# PhotonOnAStick.net
KiCad netlist of a schematic drawn in EAGLE
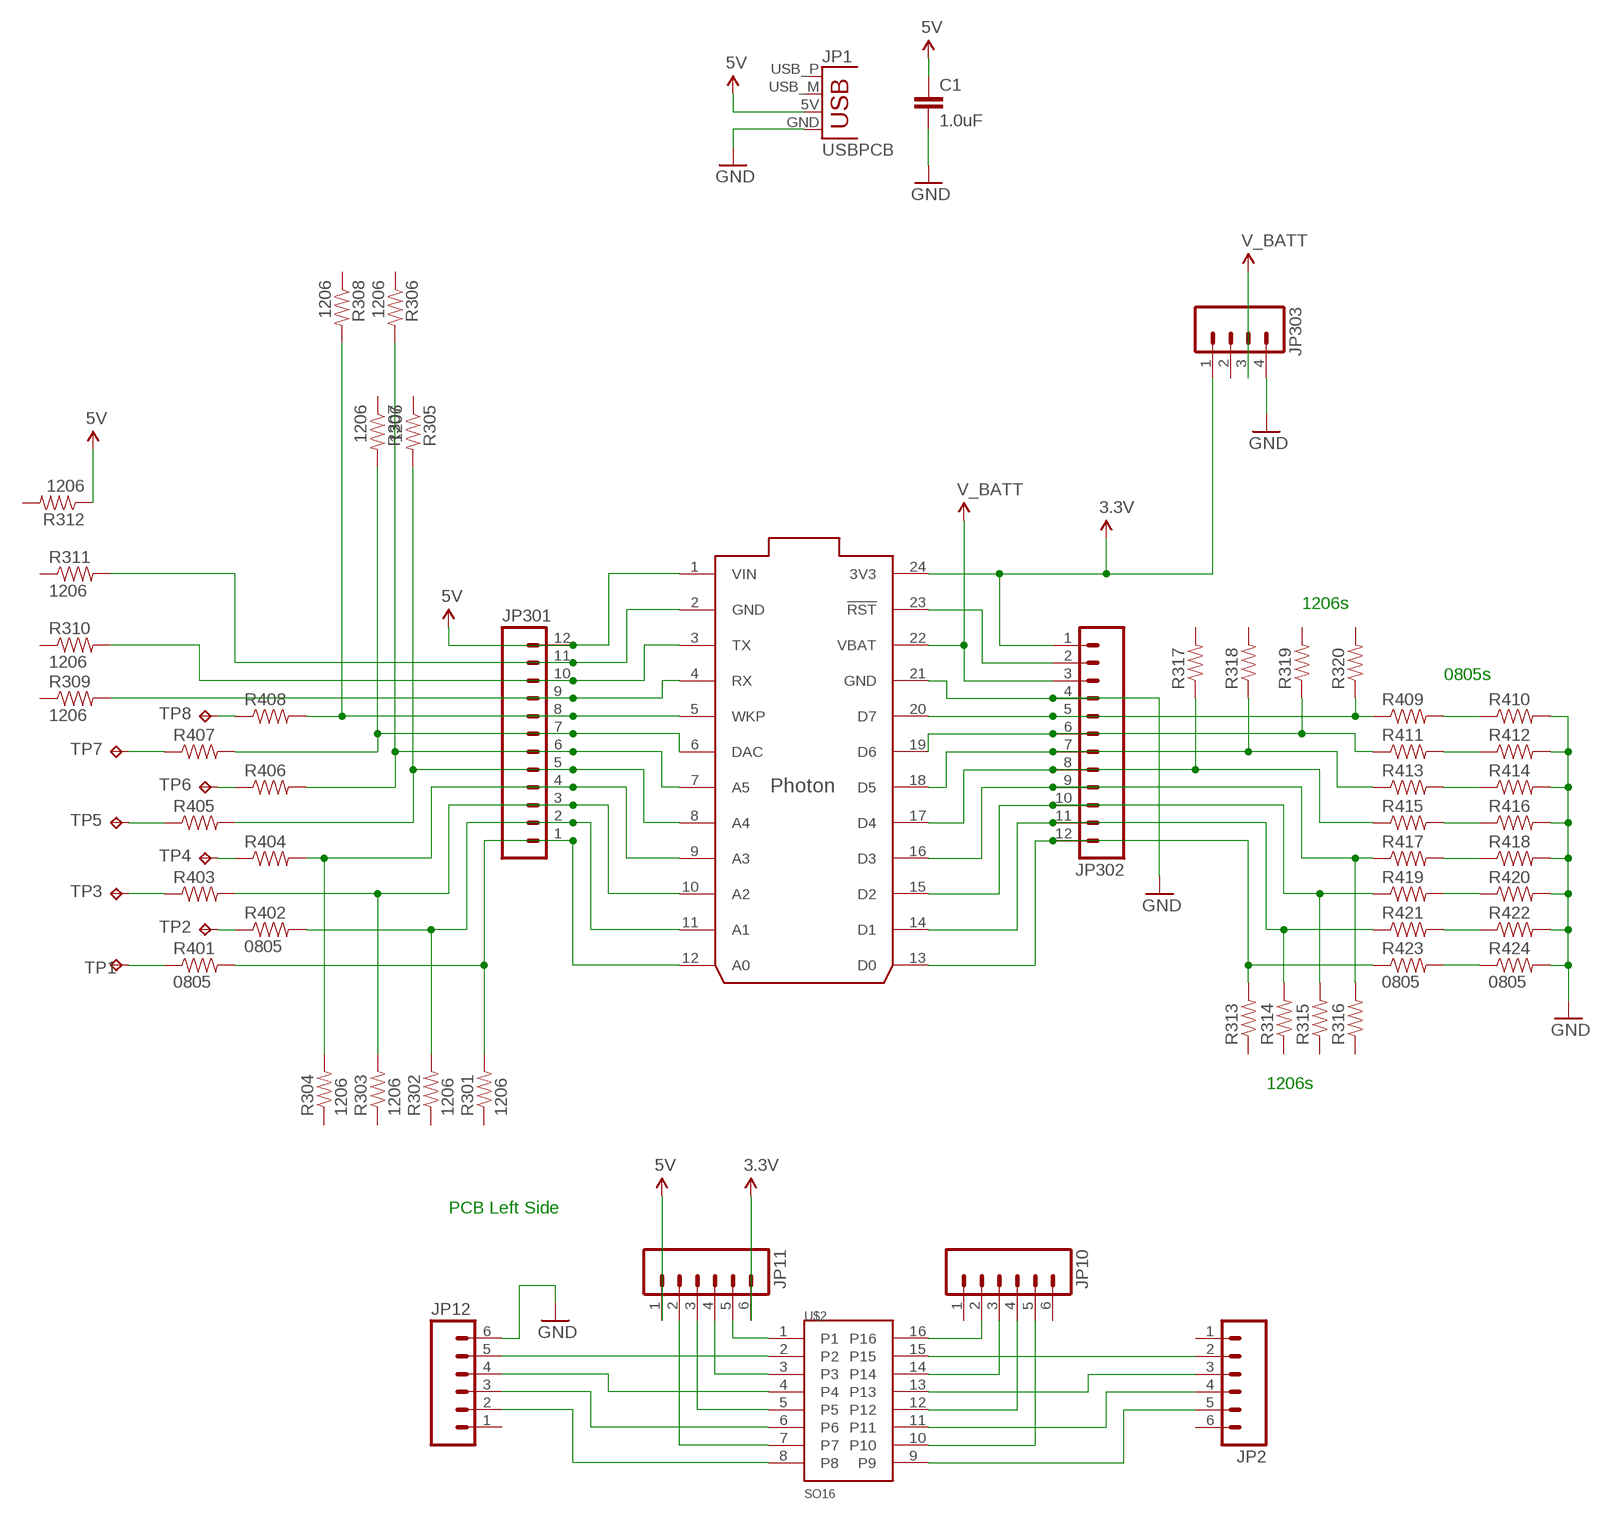
[diagram p0: schematic, sheet 1, part 1 of 2]
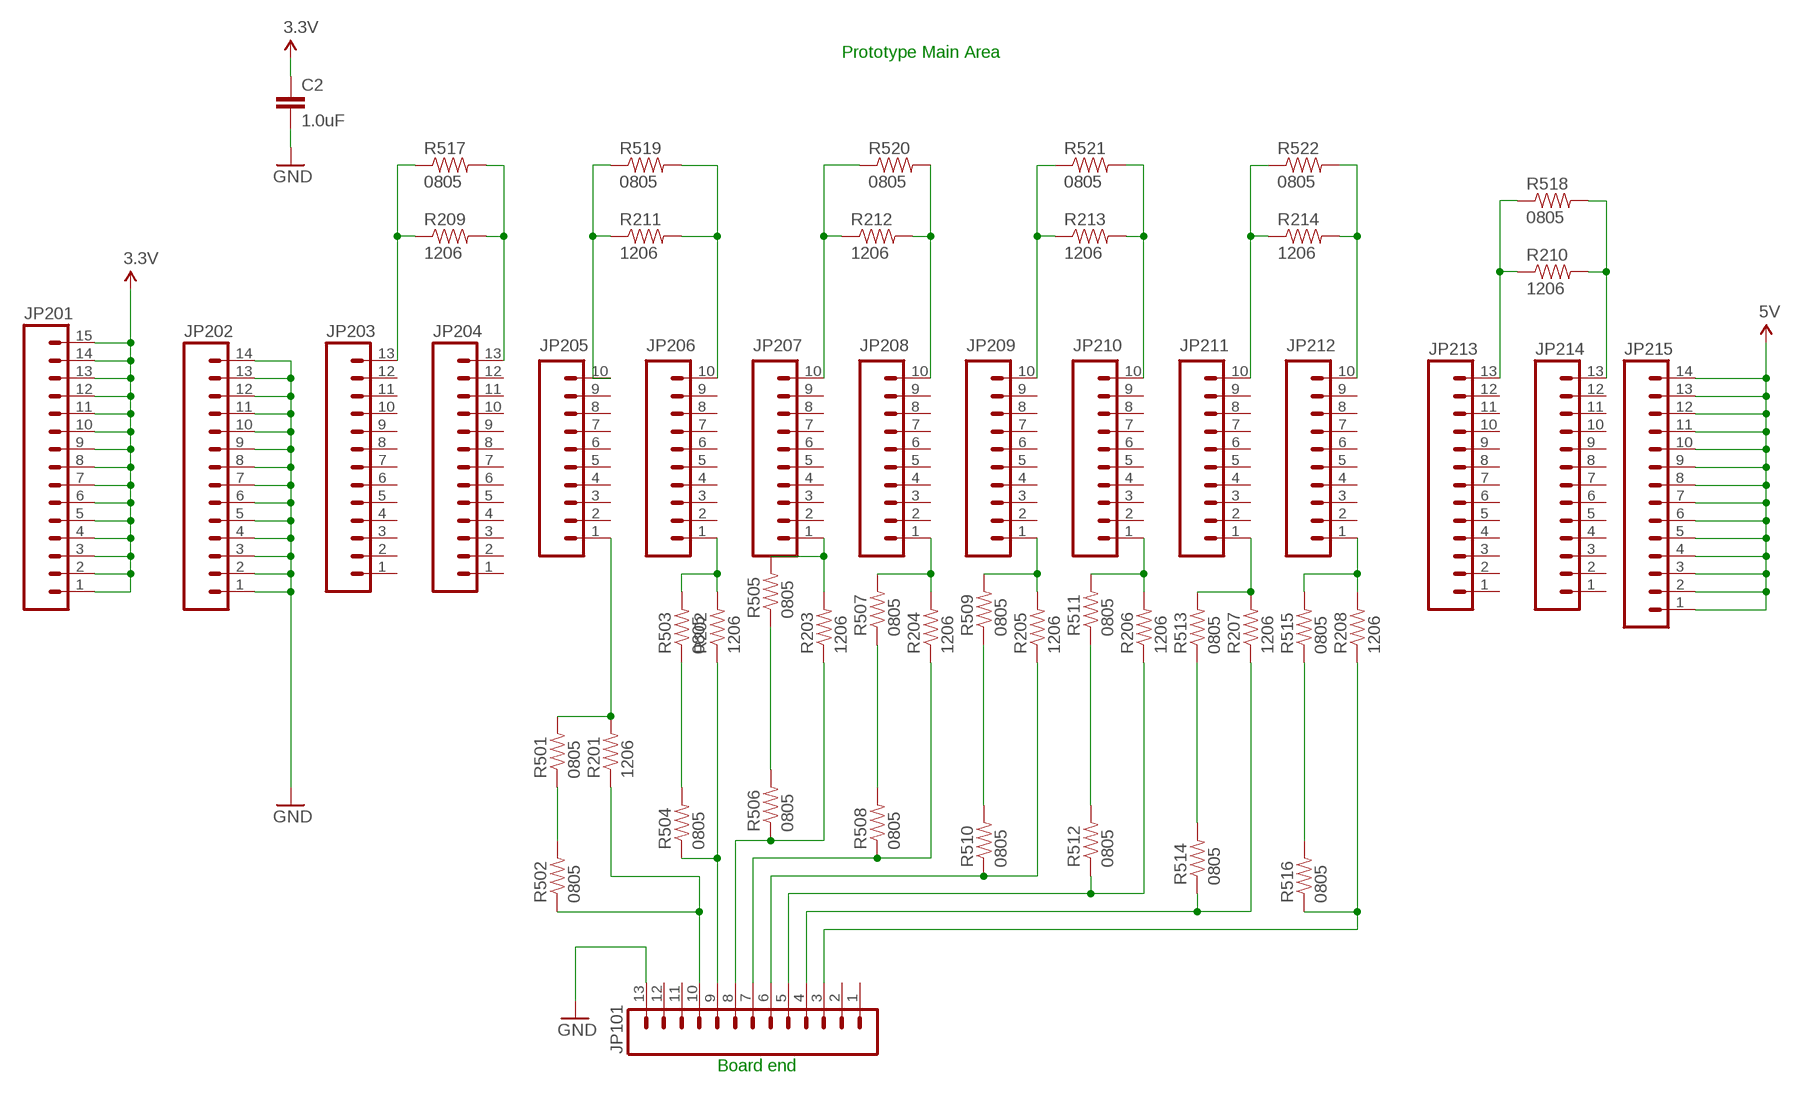
[diagram p1: schematic, sheet 1, part 2 of 2]

(export (version "E")
  (design (tool "Eeschema 10.0.6"))
  (components
    (comp (ref "C1")
      (value "1.0uF")
      (footprint "eagle-import:0805-CAP")
      (libsource (lib "eagle-import") (part "1.0UF-25V-+80/-20(0805){dblquote}"))
    )
    (comp (ref "C2")
      (value "1.0uF")
      (footprint "eagle-import:0805-CAP")
      (libsource (lib "eagle-import") (part "1.0UF-25V-+80/-20(0805){dblquote}"))
    )
    (comp (ref "JP1")
      (value "USBPCB")
      (footprint "eagle-import:USB-A-PCB")
      (libsource (lib "eagle-import") (part "USBPCB"))
    )
    (comp (ref "JP2")
      (value "M06SILK_FEMALE_PTH")
      (footprint "eagle-import:1X06")
      (libsource (lib "eagle-import") (part "M06SILK_FEMALE_PTH"))
    )
    (comp (ref "JP10")
      (value "M06SILK_FEMALE_PTH")
      (footprint "eagle-import:1X06")
      (libsource (lib "eagle-import") (part "M06SILK_FEMALE_PTH"))
    )
    (comp (ref "JP11")
      (value "M06SILK_FEMALE_PTH")
      (footprint "eagle-import:1X06")
      (libsource (lib "eagle-import") (part "M06SILK_FEMALE_PTH"))
    )
    (comp (ref "JP12")
      (value "M06SILK_FEMALE_PTH")
      (footprint "eagle-import:1X06")
      (libsource (lib "eagle-import") (part "M06SILK_FEMALE_PTH"))
    )
    (comp (ref "JP101")
      (value "M13")
      (footprint "eagle-import:1X13")
      (libsource (lib "eagle-import") (part "M13"))
    )
    (comp (ref "JP201")
      (value "M15")
      (footprint "eagle-import:1X15")
      (libsource (lib "eagle-import") (part "M15"))
    )
    (comp (ref "JP202")
      (value "M14")
      (footprint "eagle-import:1X14")
      (libsource (lib "eagle-import") (part "M14"))
    )
    (comp (ref "JP203")
      (value "M13")
      (footprint "eagle-import:1X13")
      (libsource (lib "eagle-import") (part "M13"))
    )
    (comp (ref "JP204")
      (value "M13")
      (footprint "eagle-import:1X13")
      (libsource (lib "eagle-import") (part "M13"))
    )
    (comp (ref "JP205")
      (value "M10SILK_FEMALE_PTH")
      (footprint "eagle-import:1X10")
      (libsource (lib "eagle-import") (part "M10SILK_FEMALE_PTH"))
    )
    (comp (ref "JP206")
      (value "M10SILK_FEMALE_PTH")
      (footprint "eagle-import:1X10")
      (libsource (lib "eagle-import") (part "M10SILK_FEMALE_PTH"))
    )
    (comp (ref "JP207")
      (value "M10SILK_FEMALE_PTH")
      (footprint "eagle-import:1X10")
      (libsource (lib "eagle-import") (part "M10SILK_FEMALE_PTH"))
    )
    (comp (ref "JP208")
      (value "M10SILK_FEMALE_PTH")
      (footprint "eagle-import:1X10")
      (libsource (lib "eagle-import") (part "M10SILK_FEMALE_PTH"))
    )
    (comp (ref "JP209")
      (value "M10SILK_FEMALE_PTH")
      (footprint "eagle-import:1X10")
      (libsource (lib "eagle-import") (part "M10SILK_FEMALE_PTH"))
    )
    (comp (ref "JP210")
      (value "M10SILK_FEMALE_PTH")
      (footprint "eagle-import:1X10")
      (libsource (lib "eagle-import") (part "M10SILK_FEMALE_PTH"))
    )
    (comp (ref "JP211")
      (value "M10SILK_FEMALE_PTH")
      (footprint "eagle-import:1X10")
      (libsource (lib "eagle-import") (part "M10SILK_FEMALE_PTH"))
    )
    (comp (ref "JP212")
      (value "M10SILK_FEMALE_PTH")
      (footprint "eagle-import:1X10")
      (libsource (lib "eagle-import") (part "M10SILK_FEMALE_PTH"))
    )
    (comp (ref "JP213")
      (value "M13")
      (footprint "eagle-import:1X13")
      (libsource (lib "eagle-import") (part "M13"))
    )
    (comp (ref "JP214")
      (value "M13")
      (footprint "eagle-import:1X13")
      (libsource (lib "eagle-import") (part "M13"))
    )
    (comp (ref "JP215")
      (value "M14")
      (footprint "eagle-import:1X14")
      (libsource (lib "eagle-import") (part "M14"))
    )
    (comp (ref "JP301")
      (value "M12PTH")
      (footprint "eagle-import:1X12")
      (libsource (lib "eagle-import") (part "M12PTH"))
    )
    (comp (ref "JP302")
      (value "M12PTH")
      (footprint "eagle-import:1X12")
      (libsource (lib "eagle-import") (part "M12PTH"))
    )
    (comp (ref "JP303")
      (value "M04PTH")
      (footprint "eagle-import:1X04")
      (libsource (lib "eagle-import") (part "M04PTH"))
    )
    (comp (ref "R201")
      (value "1206")
      (footprint "eagle-import:1206")
      (libsource (lib "eagle-import") (part "RESISTOR1206"))
    )
    (comp (ref "R202")
      (value "1206")
      (footprint "eagle-import:1206")
      (libsource (lib "eagle-import") (part "RESISTOR1206"))
    )
    (comp (ref "R203")
      (value "1206")
      (footprint "eagle-import:1206")
      (libsource (lib "eagle-import") (part "RESISTOR1206"))
    )
    (comp (ref "R204")
      (value "1206")
      (footprint "eagle-import:1206")
      (libsource (lib "eagle-import") (part "RESISTOR1206"))
    )
    (comp (ref "R205")
      (value "1206")
      (footprint "eagle-import:1206")
      (libsource (lib "eagle-import") (part "RESISTOR1206"))
    )
    (comp (ref "R206")
      (value "1206")
      (footprint "eagle-import:1206")
      (libsource (lib "eagle-import") (part "RESISTOR1206"))
    )
    (comp (ref "R207")
      (value "1206")
      (footprint "eagle-import:1206")
      (libsource (lib "eagle-import") (part "RESISTOR1206"))
    )
    (comp (ref "R208")
      (value "1206")
      (footprint "eagle-import:1206")
      (libsource (lib "eagle-import") (part "RESISTOR1206"))
    )
    (comp (ref "R209")
      (value "1206")
      (footprint "eagle-import:1206")
      (libsource (lib "eagle-import") (part "RESISTOR1206"))
    )
    (comp (ref "R210")
      (value "1206")
      (footprint "eagle-import:1206")
      (libsource (lib "eagle-import") (part "RESISTOR1206"))
    )
    (comp (ref "R211")
      (value "1206")
      (footprint "eagle-import:1206")
      (libsource (lib "eagle-import") (part "RESISTOR1206"))
    )
    (comp (ref "R212")
      (value "1206")
      (footprint "eagle-import:1206")
      (libsource (lib "eagle-import") (part "RESISTOR1206"))
    )
    (comp (ref "R213")
      (value "1206")
      (footprint "eagle-import:1206")
      (libsource (lib "eagle-import") (part "RESISTOR1206"))
    )
    (comp (ref "R214")
      (value "1206")
      (footprint "eagle-import:1206")
      (libsource (lib "eagle-import") (part "RESISTOR1206"))
    )
    (comp (ref "R301")
      (value "1206")
      (footprint "eagle-import:1206")
      (libsource (lib "eagle-import") (part "RESISTOR1206"))
    )
    (comp (ref "R302")
      (value "1206")
      (footprint "eagle-import:1206")
      (libsource (lib "eagle-import") (part "RESISTOR1206"))
    )
    (comp (ref "R303")
      (value "1206")
      (footprint "eagle-import:1206")
      (libsource (lib "eagle-import") (part "RESISTOR1206"))
    )
    (comp (ref "R304")
      (value "1206")
      (footprint "eagle-import:1206")
      (libsource (lib "eagle-import") (part "RESISTOR1206"))
    )
    (comp (ref "R305")
      (value "1206")
      (footprint "eagle-import:1206")
      (libsource (lib "eagle-import") (part "RESISTOR1206"))
    )
    (comp (ref "R306")
      (value "1206")
      (footprint "eagle-import:1206")
      (libsource (lib "eagle-import") (part "RESISTOR1206"))
    )
    (comp (ref "R307")
      (value "1206")
      (footprint "eagle-import:1206")
      (libsource (lib "eagle-import") (part "RESISTOR1206"))
    )
    (comp (ref "R308")
      (value "1206")
      (footprint "eagle-import:1206")
      (libsource (lib "eagle-import") (part "RESISTOR1206"))
    )
    (comp (ref "R309")
      (value "1206")
      (footprint "eagle-import:1206")
      (libsource (lib "eagle-import") (part "RESISTOR1206"))
    )
    (comp (ref "R310")
      (value "1206")
      (footprint "eagle-import:1206")
      (libsource (lib "eagle-import") (part "RESISTOR1206"))
    )
    (comp (ref "R311")
      (value "1206")
      (footprint "eagle-import:1206")
      (libsource (lib "eagle-import") (part "RESISTOR1206"))
    )
    (comp (ref "R312")
      (value "1206")
      (footprint "eagle-import:1206")
      (libsource (lib "eagle-import") (part "RESISTOR1206"))
    )
    (comp (ref "R313")
      (value "1206")
      (footprint "eagle-import:1206")
      (libsource (lib "eagle-import") (part "RESISTOR1206"))
    )
    (comp (ref "R314")
      (value "1206")
      (footprint "eagle-import:1206")
      (libsource (lib "eagle-import") (part "RESISTOR1206"))
    )
    (comp (ref "R315")
      (value "1206")
      (footprint "eagle-import:1206")
      (libsource (lib "eagle-import") (part "RESISTOR1206"))
    )
    (comp (ref "R316")
      (value "1206")
      (footprint "eagle-import:1206")
      (libsource (lib "eagle-import") (part "RESISTOR1206"))
    )
    (comp (ref "R317")
      (value "1206")
      (footprint "eagle-import:1206")
      (libsource (lib "eagle-import") (part "RESISTOR1206"))
    )
    (comp (ref "R318")
      (value "1206")
      (footprint "eagle-import:1206")
      (libsource (lib "eagle-import") (part "RESISTOR1206"))
    )
    (comp (ref "R319")
      (value "1206")
      (footprint "eagle-import:1206")
      (libsource (lib "eagle-import") (part "RESISTOR1206"))
    )
    (comp (ref "R320")
      (value "1206")
      (footprint "eagle-import:1206")
      (libsource (lib "eagle-import") (part "RESISTOR1206"))
    )
    (comp (ref "R401")
      (value "0805")
      (footprint "eagle-import:0805")
      (libsource (lib "eagle-import") (part "RESISTOR0805-RES"))
    )
    (comp (ref "R402")
      (value "0805")
      (footprint "eagle-import:0805")
      (libsource (lib "eagle-import") (part "RESISTOR0805-RES"))
    )
    (comp (ref "R403")
      (value "0805")
      (footprint "eagle-import:0805")
      (libsource (lib "eagle-import") (part "RESISTOR0805-RES"))
    )
    (comp (ref "R404")
      (value "0805")
      (footprint "eagle-import:0805")
      (libsource (lib "eagle-import") (part "RESISTOR0805-RES"))
    )
    (comp (ref "R405")
      (value "0805")
      (footprint "eagle-import:0805")
      (libsource (lib "eagle-import") (part "RESISTOR0805-RES"))
    )
    (comp (ref "R406")
      (value "0805")
      (footprint "eagle-import:0805")
      (libsource (lib "eagle-import") (part "RESISTOR0805-RES"))
    )
    (comp (ref "R407")
      (value "0805")
      (footprint "eagle-import:0805")
      (libsource (lib "eagle-import") (part "RESISTOR0805-RES"))
    )
    (comp (ref "R408")
      (value "0805")
      (footprint "eagle-import:0805")
      (libsource (lib "eagle-import") (part "RESISTOR0805-RES"))
    )
    (comp (ref "R409")
      (value "0805")
      (footprint "eagle-import:0805")
      (libsource (lib "eagle-import") (part "RESISTOR0805-RES"))
    )
    (comp (ref "R410")
      (value "0805")
      (footprint "eagle-import:0805")
      (libsource (lib "eagle-import") (part "RESISTOR0805-RES"))
    )
    (comp (ref "R411")
      (value "0805")
      (footprint "eagle-import:0805")
      (libsource (lib "eagle-import") (part "RESISTOR0805-RES"))
    )
    (comp (ref "R412")
      (value "0805")
      (footprint "eagle-import:0805")
      (libsource (lib "eagle-import") (part "RESISTOR0805-RES"))
    )
    (comp (ref "R413")
      (value "0805")
      (footprint "eagle-import:0805")
      (libsource (lib "eagle-import") (part "RESISTOR0805-RES"))
    )
    (comp (ref "R414")
      (value "0805")
      (footprint "eagle-import:0805")
      (libsource (lib "eagle-import") (part "RESISTOR0805-RES"))
    )
    (comp (ref "R415")
      (value "0805")
      (footprint "eagle-import:0805")
      (libsource (lib "eagle-import") (part "RESISTOR0805-RES"))
    )
    (comp (ref "R416")
      (value "0805")
      (footprint "eagle-import:0805")
      (libsource (lib "eagle-import") (part "RESISTOR0805-RES"))
    )
    (comp (ref "R417")
      (value "0805")
      (footprint "eagle-import:0805")
      (libsource (lib "eagle-import") (part "RESISTOR0805-RES"))
    )
    (comp (ref "R418")
      (value "0805")
      (footprint "eagle-import:0805")
      (libsource (lib "eagle-import") (part "RESISTOR0805-RES"))
    )
    (comp (ref "R419")
      (value "0805")
      (footprint "eagle-import:0805")
      (libsource (lib "eagle-import") (part "RESISTOR0805-RES"))
    )
    (comp (ref "R420")
      (value "0805")
      (footprint "eagle-import:0805")
      (libsource (lib "eagle-import") (part "RESISTOR0805-RES"))
    )
    (comp (ref "R421")
      (value "0805")
      (footprint "eagle-import:0805")
      (libsource (lib "eagle-import") (part "RESISTOR0805-RES"))
    )
    (comp (ref "R422")
      (value "0805")
      (footprint "eagle-import:0805")
      (libsource (lib "eagle-import") (part "RESISTOR0805-RES"))
    )
    (comp (ref "R423")
      (value "0805")
      (footprint "eagle-import:0805")
      (libsource (lib "eagle-import") (part "RESISTOR0805-RES"))
    )
    (comp (ref "R424")
      (value "0805")
      (footprint "eagle-import:0805")
      (libsource (lib "eagle-import") (part "RESISTOR0805-RES"))
    )
    (comp (ref "R501")
      (value "0805")
      (footprint "eagle-import:0805")
      (libsource (lib "eagle-import") (part "RESISTOR0805-RES"))
    )
    (comp (ref "R502")
      (value "0805")
      (footprint "eagle-import:0805")
      (libsource (lib "eagle-import") (part "RESISTOR0805-RES"))
    )
    (comp (ref "R503")
      (value "0805")
      (footprint "eagle-import:0805")
      (libsource (lib "eagle-import") (part "RESISTOR0805-RES"))
    )
    (comp (ref "R504")
      (value "0805")
      (footprint "eagle-import:0805")
      (libsource (lib "eagle-import") (part "RESISTOR0805-RES"))
    )
    (comp (ref "R505")
      (value "0805")
      (footprint "eagle-import:0805")
      (libsource (lib "eagle-import") (part "RESISTOR0805-RES"))
    )
    (comp (ref "R506")
      (value "0805")
      (footprint "eagle-import:0805")
      (libsource (lib "eagle-import") (part "RESISTOR0805-RES"))
    )
    (comp (ref "R507")
      (value "0805")
      (footprint "eagle-import:0805")
      (libsource (lib "eagle-import") (part "RESISTOR0805-RES"))
    )
    (comp (ref "R508")
      (value "0805")
      (footprint "eagle-import:0805")
      (libsource (lib "eagle-import") (part "RESISTOR0805-RES"))
    )
    (comp (ref "R509")
      (value "0805")
      (footprint "eagle-import:0805")
      (libsource (lib "eagle-import") (part "RESISTOR0805-RES"))
    )
    (comp (ref "R510")
      (value "0805")
      (footprint "eagle-import:0805")
      (libsource (lib "eagle-import") (part "RESISTOR0805-RES"))
    )
    (comp (ref "R511")
      (value "0805")
      (footprint "eagle-import:0805")
      (libsource (lib "eagle-import") (part "RESISTOR0805-RES"))
    )
    (comp (ref "R512")
      (value "0805")
      (footprint "eagle-import:0805")
      (libsource (lib "eagle-import") (part "RESISTOR0805-RES"))
    )
    (comp (ref "R513")
      (value "0805")
      (footprint "eagle-import:0805")
      (libsource (lib "eagle-import") (part "RESISTOR0805-RES"))
    )
    (comp (ref "R514")
      (value "0805")
      (footprint "eagle-import:0805")
      (libsource (lib "eagle-import") (part "RESISTOR0805-RES"))
    )
    (comp (ref "R515")
      (value "0805")
      (footprint "eagle-import:0805")
      (libsource (lib "eagle-import") (part "RESISTOR0805-RES"))
    )
    (comp (ref "R516")
      (value "0805")
      (footprint "eagle-import:0805")
      (libsource (lib "eagle-import") (part "RESISTOR0805-RES"))
    )
    (comp (ref "R517")
      (value "0805")
      (footprint "eagle-import:0805")
      (libsource (lib "eagle-import") (part "RESISTOR0805-RES"))
    )
    (comp (ref "R518")
      (value "0805")
      (footprint "eagle-import:0805")
      (libsource (lib "eagle-import") (part "RESISTOR0805-RES"))
    )
    (comp (ref "R519")
      (value "0805")
      (footprint "eagle-import:0805")
      (libsource (lib "eagle-import") (part "RESISTOR0805-RES"))
    )
    (comp (ref "R520")
      (value "0805")
      (footprint "eagle-import:0805")
      (libsource (lib "eagle-import") (part "RESISTOR0805-RES"))
    )
    (comp (ref "R521")
      (value "0805")
      (footprint "eagle-import:0805")
      (libsource (lib "eagle-import") (part "RESISTOR0805-RES"))
    )
    (comp (ref "R522")
      (value "0805")
      (footprint "eagle-import:0805")
      (libsource (lib "eagle-import") (part "RESISTOR0805-RES"))
    )
    (comp (ref "TP1")
      (value "TPB1,27")
      (footprint "eagle-import:B1,27")
      (libsource (lib "eagle-import") (part "TPB1,27"))
    )
    (comp (ref "TP2")
      (value "TPB1,27")
      (footprint "eagle-import:B1,27")
      (libsource (lib "eagle-import") (part "TPB1,27"))
    )
    (comp (ref "TP3")
      (value "TPB1,27")
      (footprint "eagle-import:B1,27")
      (libsource (lib "eagle-import") (part "TPB1,27"))
    )
    (comp (ref "TP4")
      (value "TPB1,27")
      (footprint "eagle-import:B1,27")
      (libsource (lib "eagle-import") (part "TPB1,27"))
    )
    (comp (ref "TP5")
      (value "TPB1,27")
      (footprint "eagle-import:B1,27")
      (libsource (lib "eagle-import") (part "TPB1,27"))
    )
    (comp (ref "TP6")
      (value "TPB1,27")
      (footprint "eagle-import:B1,27")
      (libsource (lib "eagle-import") (part "TPB1,27"))
    )
    (comp (ref "TP7")
      (value "TPB1,27")
      (footprint "eagle-import:B1,27")
      (libsource (lib "eagle-import") (part "TPB1,27"))
    )
    (comp (ref "TP8")
      (value "TPB1,27")
      (footprint "eagle-import:B1,27")
      (libsource (lib "eagle-import") (part "TPB1,27"))
    )
    (comp (ref "U$1")
      (value "PHOTON_WITH_HEADERS")
      (footprint "eagle-import:PHOTON")
      (libsource (lib "eagle-import") (part "PHOTON_WITH_HEADERS"))
    )
    (comp (ref "U$2")
      (value "SO16")
      (footprint "eagle-import:SO16")
      (libsource (lib "eagle-import") (part "SO16"))
    )
  )
  (nets
    (net (code "1") (name "3.3V") (class "Default")
      (node (ref "C2") (pin "1") (pinfunction "1_1") (pintype "passive"))
      (node (ref "JP11") (pin "6") (pinfunction "6_6") (pintype "passive"))
      (node (ref "JP201") (pin "1") (pinfunction "1_1") (pintype "passive"))
      (node (ref "JP201") (pin "10") (pinfunction "10_10") (pintype "passive"))
      (node (ref "JP201") (pin "11") (pinfunction "11_11") (pintype "passive"))
      (node (ref "JP201") (pin "12") (pinfunction "12_12") (pintype "passive"))
      (node (ref "JP201") (pin "13") (pinfunction "13_13") (pintype "passive"))
      (node (ref "JP201") (pin "14") (pinfunction "14_14") (pintype "passive"))
      (node (ref "JP201") (pin "15") (pinfunction "15_15") (pintype "passive"))
      (node (ref "JP201") (pin "2") (pinfunction "2_2") (pintype "passive"))
      (node (ref "JP201") (pin "3") (pinfunction "3_3") (pintype "passive"))
      (node (ref "JP201") (pin "4") (pinfunction "4_4") (pintype "passive"))
      (node (ref "JP201") (pin "5") (pinfunction "5_5") (pintype "passive"))
      (node (ref "JP201") (pin "6") (pinfunction "6_6") (pintype "passive"))
      (node (ref "JP201") (pin "7") (pinfunction "7_7") (pintype "passive"))
      (node (ref "JP201") (pin "8") (pinfunction "8_8") (pintype "passive"))
      (node (ref "JP201") (pin "9") (pinfunction "9_9") (pintype "passive"))
      (node (ref "JP302") (pin "1") (pinfunction "1_1") (pintype "passive"))
      (node (ref "JP303") (pin "1") (pinfunction "1_1") (pintype "passive"))
      (node (ref "U$1") (pin "24") (pinfunction "3V3_24") (pintype "power_in"))
    )
    (net (code "2") (name "5V") (class "Default")
      (node (ref "C1") (pin "1") (pinfunction "1_1") (pintype "passive"))
      (node (ref "JP1") (pin "5V") (pinfunction "VBUS_5V") (pintype "bidirectional"))
      (node (ref "JP11") (pin "1") (pinfunction "1_1") (pintype "passive"))
      (node (ref "JP215") (pin "1") (pinfunction "1_1") (pintype "passive"))
      (node (ref "JP215") (pin "10") (pinfunction "10_10") (pintype "passive"))
      (node (ref "JP215") (pin "11") (pinfunction "11_11") (pintype "passive"))
      (node (ref "JP215") (pin "12") (pinfunction "12_12") (pintype "passive"))
      (node (ref "JP215") (pin "13") (pinfunction "13_13") (pintype "passive"))
      (node (ref "JP215") (pin "14") (pinfunction "14_14") (pintype "passive"))
      (node (ref "JP215") (pin "2") (pinfunction "2_2") (pintype "passive"))
      (node (ref "JP215") (pin "3") (pinfunction "3_3") (pintype "passive"))
      (node (ref "JP215") (pin "4") (pinfunction "4_4") (pintype "passive"))
      (node (ref "JP215") (pin "5") (pinfunction "5_5") (pintype "passive"))
      (node (ref "JP215") (pin "6") (pinfunction "6_6") (pintype "passive"))
      (node (ref "JP215") (pin "7") (pinfunction "7_7") (pintype "passive"))
      (node (ref "JP215") (pin "8") (pinfunction "8_8") (pintype "passive"))
      (node (ref "JP215") (pin "9") (pinfunction "9_9") (pintype "passive"))
      (node (ref "JP301") (pin "12") (pinfunction "12_12") (pintype "passive"))
      (node (ref "R312") (pin "1") (pinfunction "1_1") (pintype "passive"))
      (node (ref "U$1") (pin "1") (pinfunction "VIN_1") (pintype "power_in"))
    )
    (net (code "3") (name "GND") (class "Default")
      (node (ref "C1") (pin "2") (pinfunction "2_2") (pintype "passive"))
      (node (ref "C2") (pin "2") (pinfunction "2_2") (pintype "passive"))
      (node (ref "JP1") (pin "GND") (pinfunction "GND_GND") (pintype "bidirectional"))
      (node (ref "JP101") (pin "13") (pinfunction "13_13") (pintype "passive"))
      (node (ref "JP12") (pin "6") (pinfunction "6_6") (pintype "passive"))
      (node (ref "JP202") (pin "1") (pinfunction "1_1") (pintype "passive"))
      (node (ref "JP202") (pin "10") (pinfunction "10_10") (pintype "passive"))
      (node (ref "JP202") (pin "11") (pinfunction "11_11") (pintype "passive"))
      (node (ref "JP202") (pin "12") (pinfunction "12_12") (pintype "passive"))
      (node (ref "JP202") (pin "13") (pinfunction "13_13") (pintype "passive"))
      (node (ref "JP202") (pin "14") (pinfunction "14_14") (pintype "passive"))
      (node (ref "JP202") (pin "2") (pinfunction "2_2") (pintype "passive"))
      (node (ref "JP202") (pin "3") (pinfunction "3_3") (pintype "passive"))
      (node (ref "JP202") (pin "4") (pinfunction "4_4") (pintype "passive"))
      (node (ref "JP202") (pin "5") (pinfunction "5_5") (pintype "passive"))
      (node (ref "JP202") (pin "6") (pinfunction "6_6") (pintype "passive"))
      (node (ref "JP202") (pin "7") (pinfunction "7_7") (pintype "passive"))
      (node (ref "JP202") (pin "8") (pinfunction "8_8") (pintype "passive"))
      (node (ref "JP202") (pin "9") (pinfunction "9_9") (pintype "passive"))
      (node (ref "JP302") (pin "4") (pinfunction "4_4") (pintype "passive"))
      (node (ref "JP303") (pin "4") (pinfunction "4_4") (pintype "passive"))
      (node (ref "R410") (pin "2") (pinfunction "2_2") (pintype "passive"))
      (node (ref "R412") (pin "2") (pinfunction "2_2") (pintype "passive"))
      (node (ref "R414") (pin "2") (pinfunction "2_2") (pintype "passive"))
      (node (ref "R416") (pin "2") (pinfunction "2_2") (pintype "passive"))
      (node (ref "R418") (pin "2") (pinfunction "2_2") (pintype "passive"))
      (node (ref "R420") (pin "2") (pinfunction "2_2") (pintype "passive"))
      (node (ref "R422") (pin "2") (pinfunction "2_2") (pintype "passive"))
      (node (ref "R424") (pin "2") (pinfunction "2_2") (pintype "passive"))
      (node (ref "U$1") (pin "21") (pinfunction "GND_21") (pintype "power_in"))
    )
    (net (code "4") (name "Net-(JP101-Pad3)") (class "Default")
      (node (ref "JP101") (pin "3") (pinfunction "3_3") (pintype "passive"))
      (node (ref "R208") (pin "1") (pinfunction "1_1") (pintype "passive"))
      (node (ref "R516") (pin "1") (pinfunction "1_1") (pintype "passive"))
    )
    (net (code "5") (name "Net-(JP101-Pad4)") (class "Default")
      (node (ref "JP101") (pin "4") (pinfunction "4_4") (pintype "passive"))
      (node (ref "R207") (pin "1") (pinfunction "1_1") (pintype "passive"))
      (node (ref "R514") (pin "1") (pinfunction "1_1") (pintype "passive"))
    )
    (net (code "6") (name "Net-(JP101-Pad5)") (class "Default")
      (node (ref "JP101") (pin "5") (pinfunction "5_5") (pintype "passive"))
      (node (ref "R206") (pin "1") (pinfunction "1_1") (pintype "passive"))
      (node (ref "R512") (pin "1") (pinfunction "1_1") (pintype "passive"))
    )
    (net (code "7") (name "Net-(JP101-Pad6)") (class "Default")
      (node (ref "JP101") (pin "6") (pinfunction "6_6") (pintype "passive"))
      (node (ref "R205") (pin "1") (pinfunction "1_1") (pintype "passive"))
      (node (ref "R510") (pin "1") (pinfunction "1_1") (pintype "passive"))
    )
    (net (code "8") (name "Net-(JP101-Pad7)") (class "Default")
      (node (ref "JP101") (pin "7") (pinfunction "7_7") (pintype "passive"))
      (node (ref "R204") (pin "1") (pinfunction "1_1") (pintype "passive"))
      (node (ref "R508") (pin "1") (pinfunction "1_1") (pintype "passive"))
    )
    (net (code "9") (name "Net-(JP101-Pad8)") (class "Default")
      (node (ref "JP101") (pin "8") (pinfunction "8_8") (pintype "passive"))
      (node (ref "R203") (pin "1") (pinfunction "1_1") (pintype "passive"))
      (node (ref "R506") (pin "1") (pinfunction "1_1") (pintype "passive"))
    )
    (net (code "10") (name "Net-(JP101-Pad9)") (class "Default")
      (node (ref "JP101") (pin "9") (pinfunction "9_9") (pintype "passive"))
      (node (ref "R202") (pin "1") (pinfunction "1_1") (pintype "passive"))
      (node (ref "R504") (pin "1") (pinfunction "1_1") (pintype "passive"))
    )
    (net (code "11") (name "Net-(JP101-Pad10)") (class "Default")
      (node (ref "JP101") (pin "10") (pinfunction "10_10") (pintype "passive"))
      (node (ref "R201") (pin "1") (pinfunction "1_1") (pintype "passive"))
      (node (ref "R502") (pin "1") (pinfunction "1_1") (pintype "passive"))
    )
    (net (code "12") (name "Net-(JP203-Pad13)") (class "Default")
      (node (ref "JP203") (pin "13") (pinfunction "13_13") (pintype "passive"))
      (node (ref "R209") (pin "1") (pinfunction "1_1") (pintype "passive"))
      (node (ref "R517") (pin "1") (pinfunction "1_1") (pintype "passive"))
    )
    (net (code "13") (name "Net-(JP204-Pad13)") (class "Default")
      (node (ref "JP204") (pin "13") (pinfunction "13_13") (pintype "passive"))
      (node (ref "R209") (pin "2") (pinfunction "2_2") (pintype "passive"))
      (node (ref "R517") (pin "2") (pinfunction "2_2") (pintype "passive"))
    )
    (net (code "14") (name "Net-(JP205-Pad1)") (class "Default")
      (node (ref "JP205") (pin "1") (pinfunction "1_1") (pintype "passive"))
      (node (ref "R201") (pin "2") (pinfunction "2_2") (pintype "passive"))
      (node (ref "R501") (pin "2") (pinfunction "2_2") (pintype "passive"))
    )
    (net (code "15") (name "Net-(JP205-Pad10)") (class "Default")
      (node (ref "JP205") (pin "10") (pinfunction "10_10") (pintype "passive"))
      (node (ref "R211") (pin "1") (pinfunction "1_1") (pintype "passive"))
      (node (ref "R519") (pin "1") (pinfunction "1_1") (pintype "passive"))
    )
    (net (code "16") (name "Net-(JP206-Pad1)") (class "Default")
      (node (ref "JP206") (pin "1") (pinfunction "1_1") (pintype "passive"))
      (node (ref "R202") (pin "2") (pinfunction "2_2") (pintype "passive"))
      (node (ref "R503") (pin "2") (pinfunction "2_2") (pintype "passive"))
    )
    (net (code "17") (name "Net-(JP206-Pad10)") (class "Default")
      (node (ref "JP206") (pin "10") (pinfunction "10_10") (pintype "passive"))
      (node (ref "R211") (pin "2") (pinfunction "2_2") (pintype "passive"))
      (node (ref "R519") (pin "2") (pinfunction "2_2") (pintype "passive"))
    )
    (net (code "18") (name "Net-(JP207-Pad1)") (class "Default")
      (node (ref "JP207") (pin "1") (pinfunction "1_1") (pintype "passive"))
      (node (ref "R203") (pin "2") (pinfunction "2_2") (pintype "passive"))
      (node (ref "R505") (pin "2") (pinfunction "2_2") (pintype "passive"))
    )
    (net (code "19") (name "Net-(JP207-Pad10)") (class "Default")
      (node (ref "JP207") (pin "10") (pinfunction "10_10") (pintype "passive"))
      (node (ref "R212") (pin "1") (pinfunction "1_1") (pintype "passive"))
      (node (ref "R520") (pin "1") (pinfunction "1_1") (pintype "passive"))
    )
    (net (code "20") (name "Net-(JP208-Pad1)") (class "Default")
      (node (ref "JP208") (pin "1") (pinfunction "1_1") (pintype "passive"))
      (node (ref "R204") (pin "2") (pinfunction "2_2") (pintype "passive"))
      (node (ref "R507") (pin "2") (pinfunction "2_2") (pintype "passive"))
    )
    (net (code "21") (name "Net-(JP208-Pad10)") (class "Default")
      (node (ref "JP208") (pin "10") (pinfunction "10_10") (pintype "passive"))
      (node (ref "R212") (pin "2") (pinfunction "2_2") (pintype "passive"))
      (node (ref "R520") (pin "2") (pinfunction "2_2") (pintype "passive"))
    )
    (net (code "22") (name "Net-(JP209-Pad1)") (class "Default")
      (node (ref "JP209") (pin "1") (pinfunction "1_1") (pintype "passive"))
      (node (ref "R205") (pin "2") (pinfunction "2_2") (pintype "passive"))
      (node (ref "R509") (pin "2") (pinfunction "2_2") (pintype "passive"))
    )
    (net (code "23") (name "Net-(JP209-Pad10)") (class "Default")
      (node (ref "JP209") (pin "10") (pinfunction "10_10") (pintype "passive"))
      (node (ref "R213") (pin "1") (pinfunction "1_1") (pintype "passive"))
      (node (ref "R521") (pin "1") (pinfunction "1_1") (pintype "passive"))
    )
    (net (code "24") (name "Net-(JP210-Pad1)") (class "Default")
      (node (ref "JP210") (pin "1") (pinfunction "1_1") (pintype "passive"))
      (node (ref "R206") (pin "2") (pinfunction "2_2") (pintype "passive"))
      (node (ref "R511") (pin "2") (pinfunction "2_2") (pintype "passive"))
    )
    (net (code "25") (name "Net-(JP210-Pad10)") (class "Default")
      (node (ref "JP210") (pin "10") (pinfunction "10_10") (pintype "passive"))
      (node (ref "R213") (pin "2") (pinfunction "2_2") (pintype "passive"))
      (node (ref "R521") (pin "2") (pinfunction "2_2") (pintype "passive"))
    )
    (net (code "26") (name "Net-(JP211-Pad1)") (class "Default")
      (node (ref "JP211") (pin "1") (pinfunction "1_1") (pintype "passive"))
      (node (ref "R207") (pin "2") (pinfunction "2_2") (pintype "passive"))
      (node (ref "R513") (pin "2") (pinfunction "2_2") (pintype "passive"))
    )
    (net (code "27") (name "Net-(JP211-Pad10)") (class "Default")
      (node (ref "JP211") (pin "10") (pinfunction "10_10") (pintype "passive"))
      (node (ref "R214") (pin "1") (pinfunction "1_1") (pintype "passive"))
      (node (ref "R522") (pin "1") (pinfunction "1_1") (pintype "passive"))
    )
    (net (code "28") (name "Net-(JP212-Pad1)") (class "Default")
      (node (ref "JP212") (pin "1") (pinfunction "1_1") (pintype "passive"))
      (node (ref "R208") (pin "2") (pinfunction "2_2") (pintype "passive"))
      (node (ref "R515") (pin "2") (pinfunction "2_2") (pintype "passive"))
    )
    (net (code "29") (name "Net-(JP212-Pad10)") (class "Default")
      (node (ref "JP212") (pin "10") (pinfunction "10_10") (pintype "passive"))
      (node (ref "R214") (pin "2") (pinfunction "2_2") (pintype "passive"))
      (node (ref "R522") (pin "2") (pinfunction "2_2") (pintype "passive"))
    )
    (net (code "30") (name "Net-(JP213-Pad13)") (class "Default")
      (node (ref "JP213") (pin "13") (pinfunction "13_13") (pintype "passive"))
      (node (ref "R210") (pin "1") (pinfunction "1_1") (pintype "passive"))
      (node (ref "R518") (pin "1") (pinfunction "1_1") (pintype "passive"))
    )
    (net (code "31") (name "Net-(JP214-Pad13)") (class "Default")
      (node (ref "JP214") (pin "13") (pinfunction "13_13") (pintype "passive"))
      (node (ref "R210") (pin "2") (pinfunction "2_2") (pintype "passive"))
      (node (ref "R518") (pin "2") (pinfunction "2_2") (pintype "passive"))
    )
    (net (code "32") (name "Net-(JP301-Pad11)") (class "Default")
      (node (ref "JP301") (pin "11") (pinfunction "11_11") (pintype "passive"))
      (node (ref "R311") (pin "2") (pinfunction "2_2") (pintype "passive"))
      (node (ref "U$1") (pin "2") (pinfunction "GND_2") (pintype "power_in"))
    )
    (net (code "33") (name "Net-(R401-Pad1)") (class "Default")
      (node (ref "R401") (pin "1") (pinfunction "1_1") (pintype "passive"))
      (node (ref "TP1") (pin "TP") (pinfunction "TP_TP") (pintype "input"))
    )
    (net (code "34") (name "Net-(R402-Pad1)") (class "Default")
      (node (ref "R402") (pin "1") (pinfunction "1_1") (pintype "passive"))
      (node (ref "TP2") (pin "TP") (pinfunction "TP_TP") (pintype "input"))
    )
    (net (code "35") (name "Net-(R403-Pad1)") (class "Default")
      (node (ref "R403") (pin "1") (pinfunction "1_1") (pintype "passive"))
      (node (ref "TP3") (pin "TP") (pinfunction "TP_TP") (pintype "input"))
    )
    (net (code "36") (name "Net-(R404-Pad1)") (class "Default")
      (node (ref "R404") (pin "1") (pinfunction "1_1") (pintype "passive"))
      (node (ref "TP4") (pin "TP") (pinfunction "TP_TP") (pintype "input"))
    )
    (net (code "37") (name "Net-(R405-Pad1)") (class "Default")
      (node (ref "R405") (pin "1") (pinfunction "1_1") (pintype "passive"))
      (node (ref "TP5") (pin "TP") (pinfunction "TP_TP") (pintype "input"))
    )
    (net (code "38") (name "Net-(R406-Pad1)") (class "Default")
      (node (ref "R406") (pin "1") (pinfunction "1_1") (pintype "passive"))
      (node (ref "TP6") (pin "TP") (pinfunction "TP_TP") (pintype "input"))
    )
    (net (code "39") (name "Net-(R407-Pad1)") (class "Default")
      (node (ref "R407") (pin "1") (pinfunction "1_1") (pintype "passive"))
      (node (ref "TP7") (pin "TP") (pinfunction "TP_TP") (pintype "input"))
    )
    (net (code "40") (name "Net-(R408-Pad1)") (class "Default")
      (node (ref "R408") (pin "1") (pinfunction "1_1") (pintype "passive"))
      (node (ref "TP8") (pin "TP") (pinfunction "TP_TP") (pintype "input"))
    )
    (net (code "41") (name "Net-(R409-Pad2)") (class "Default")
      (node (ref "R409") (pin "2") (pinfunction "2_2") (pintype "passive"))
      (node (ref "R410") (pin "1") (pinfunction "1_1") (pintype "passive"))
    )
    (net (code "42") (name "Net-(R411-Pad2)") (class "Default")
      (node (ref "R411") (pin "2") (pinfunction "2_2") (pintype "passive"))
      (node (ref "R412") (pin "1") (pinfunction "1_1") (pintype "passive"))
    )
    (net (code "43") (name "Net-(R413-Pad2)") (class "Default")
      (node (ref "R413") (pin "2") (pinfunction "2_2") (pintype "passive"))
      (node (ref "R414") (pin "1") (pinfunction "1_1") (pintype "passive"))
    )
    (net (code "44") (name "Net-(R415-Pad2)") (class "Default")
      (node (ref "R415") (pin "2") (pinfunction "2_2") (pintype "passive"))
      (node (ref "R416") (pin "1") (pinfunction "1_1") (pintype "passive"))
    )
    (net (code "45") (name "Net-(R417-Pad2)") (class "Default")
      (node (ref "R417") (pin "2") (pinfunction "2_2") (pintype "passive"))
      (node (ref "R418") (pin "1") (pinfunction "1_1") (pintype "passive"))
    )
    (net (code "46") (name "Net-(R419-Pad2)") (class "Default")
      (node (ref "R419") (pin "2") (pinfunction "2_2") (pintype "passive"))
      (node (ref "R420") (pin "1") (pinfunction "1_1") (pintype "passive"))
    )
    (net (code "47") (name "Net-(R421-Pad2)") (class "Default")
      (node (ref "R421") (pin "2") (pinfunction "2_2") (pintype "passive"))
      (node (ref "R422") (pin "1") (pinfunction "1_1") (pintype "passive"))
    )
    (net (code "48") (name "Net-(R423-Pad2)") (class "Default")
      (node (ref "R423") (pin "2") (pinfunction "2_2") (pintype "passive"))
      (node (ref "R424") (pin "1") (pinfunction "1_1") (pintype "passive"))
    )
    (net (code "49") (name "Net-(R501-Pad1)") (class "Default")
      (node (ref "R501") (pin "1") (pinfunction "1_1") (pintype "passive"))
      (node (ref "R502") (pin "2") (pinfunction "2_2") (pintype "passive"))
    )
    (net (code "50") (name "Net-(R503-Pad1)") (class "Default")
      (node (ref "R503") (pin "1") (pinfunction "1_1") (pintype "passive"))
      (node (ref "R504") (pin "2") (pinfunction "2_2") (pintype "passive"))
    )
    (net (code "51") (name "Net-(R505-Pad1)") (class "Default")
      (node (ref "R505") (pin "1") (pinfunction "1_1") (pintype "passive"))
      (node (ref "R506") (pin "2") (pinfunction "2_2") (pintype "passive"))
    )
    (net (code "52") (name "Net-(R507-Pad1)") (class "Default")
      (node (ref "R507") (pin "1") (pinfunction "1_1") (pintype "passive"))
      (node (ref "R508") (pin "2") (pinfunction "2_2") (pintype "passive"))
    )
    (net (code "53") (name "Net-(R509-Pad1)") (class "Default")
      (node (ref "R509") (pin "1") (pinfunction "1_1") (pintype "passive"))
      (node (ref "R510") (pin "2") (pinfunction "2_2") (pintype "passive"))
    )
    (net (code "54") (name "Net-(R511-Pad1)") (class "Default")
      (node (ref "R511") (pin "1") (pinfunction "1_1") (pintype "passive"))
      (node (ref "R512") (pin "2") (pinfunction "2_2") (pintype "passive"))
    )
    (net (code "55") (name "Net-(R513-Pad1)") (class "Default")
      (node (ref "R513") (pin "1") (pinfunction "1_1") (pintype "passive"))
      (node (ref "R514") (pin "2") (pinfunction "2_2") (pintype "passive"))
    )
    (net (code "56") (name "Net-(R515-Pad1)") (class "Default")
      (node (ref "R515") (pin "1") (pinfunction "1_1") (pintype "passive"))
      (node (ref "R516") (pin "2") (pinfunction "2_2") (pintype "passive"))
    )
    (net (code "57") (name "Net-(U$1-A0)") (class "Default")
      (node (ref "JP301") (pin "1") (pinfunction "1_1") (pintype "passive"))
      (node (ref "R301") (pin "2") (pinfunction "2_2") (pintype "passive"))
      (node (ref "R401") (pin "2") (pinfunction "2_2") (pintype "passive"))
      (node (ref "U$1") (pin "12") (pinfunction "A0_12") (pintype "bidirectional"))
    )
    (net (code "58") (name "Net-(U$1-A1)") (class "Default")
      (node (ref "JP301") (pin "2") (pinfunction "2_2") (pintype "passive"))
      (node (ref "R302") (pin "2") (pinfunction "2_2") (pintype "passive"))
      (node (ref "R402") (pin "2") (pinfunction "2_2") (pintype "passive"))
      (node (ref "U$1") (pin "11") (pinfunction "A1_11") (pintype "bidirectional"))
    )
    (net (code "59") (name "Net-(U$1-A2)") (class "Default")
      (node (ref "JP301") (pin "3") (pinfunction "3_3") (pintype "passive"))
      (node (ref "R303") (pin "2") (pinfunction "2_2") (pintype "passive"))
      (node (ref "R403") (pin "2") (pinfunction "2_2") (pintype "passive"))
      (node (ref "U$1") (pin "10") (pinfunction "A2_10") (pintype "bidirectional"))
    )
    (net (code "60") (name "Net-(U$1-A3)") (class "Default")
      (node (ref "JP301") (pin "4") (pinfunction "4_4") (pintype "passive"))
      (node (ref "R304") (pin "2") (pinfunction "2_2") (pintype "passive"))
      (node (ref "R404") (pin "2") (pinfunction "2_2") (pintype "passive"))
      (node (ref "U$1") (pin "9") (pinfunction "A3_9") (pintype "bidirectional"))
    )
    (net (code "61") (name "Net-(U$1-A4)") (class "Default")
      (node (ref "JP301") (pin "5") (pinfunction "5_5") (pintype "passive"))
      (node (ref "R305") (pin "2") (pinfunction "2_2") (pintype "passive"))
      (node (ref "R405") (pin "2") (pinfunction "2_2") (pintype "passive"))
      (node (ref "U$1") (pin "8") (pinfunction "A4_8") (pintype "bidirectional"))
    )
    (net (code "62") (name "Net-(U$1-A5)") (class "Default")
      (node (ref "JP301") (pin "6") (pinfunction "6_6") (pintype "passive"))
      (node (ref "R306") (pin "2") (pinfunction "2_2") (pintype "passive"))
      (node (ref "R406") (pin "2") (pinfunction "2_2") (pintype "passive"))
      (node (ref "U$1") (pin "7") (pinfunction "A5_7") (pintype "bidirectional"))
    )
    (net (code "63") (name "Net-(U$1-D0)") (class "Default")
      (node (ref "JP302") (pin "12") (pinfunction "12_12") (pintype "passive"))
      (node (ref "R313") (pin "2") (pinfunction "2_2") (pintype "passive"))
      (node (ref "R423") (pin "1") (pinfunction "1_1") (pintype "passive"))
      (node (ref "U$1") (pin "13") (pinfunction "D0_13") (pintype "bidirectional"))
    )
    (net (code "64") (name "Net-(U$1-D1)") (class "Default")
      (node (ref "JP302") (pin "11") (pinfunction "11_11") (pintype "passive"))
      (node (ref "R314") (pin "2") (pinfunction "2_2") (pintype "passive"))
      (node (ref "R421") (pin "1") (pinfunction "1_1") (pintype "passive"))
      (node (ref "U$1") (pin "14") (pinfunction "D1_14") (pintype "bidirectional"))
    )
    (net (code "65") (name "Net-(U$1-D2)") (class "Default")
      (node (ref "JP302") (pin "10") (pinfunction "10_10") (pintype "passive"))
      (node (ref "R315") (pin "2") (pinfunction "2_2") (pintype "passive"))
      (node (ref "R419") (pin "1") (pinfunction "1_1") (pintype "passive"))
      (node (ref "U$1") (pin "15") (pinfunction "D2_15") (pintype "bidirectional"))
    )
    (net (code "66") (name "Net-(U$1-D3)") (class "Default")
      (node (ref "JP302") (pin "9") (pinfunction "9_9") (pintype "passive"))
      (node (ref "R316") (pin "2") (pinfunction "2_2") (pintype "passive"))
      (node (ref "R417") (pin "1") (pinfunction "1_1") (pintype "passive"))
      (node (ref "U$1") (pin "16") (pinfunction "D3_16") (pintype "bidirectional"))
    )
    (net (code "67") (name "Net-(U$1-D4)") (class "Default")
      (node (ref "JP302") (pin "8") (pinfunction "8_8") (pintype "passive"))
      (node (ref "R317") (pin "1") (pinfunction "1_1") (pintype "passive"))
      (node (ref "R415") (pin "1") (pinfunction "1_1") (pintype "passive"))
      (node (ref "U$1") (pin "17") (pinfunction "D4_17") (pintype "bidirectional"))
    )
    (net (code "68") (name "Net-(U$1-D5)") (class "Default")
      (node (ref "JP302") (pin "7") (pinfunction "7_7") (pintype "passive"))
      (node (ref "R318") (pin "1") (pinfunction "1_1") (pintype "passive"))
      (node (ref "R413") (pin "1") (pinfunction "1_1") (pintype "passive"))
      (node (ref "U$1") (pin "18") (pinfunction "D5_18") (pintype "bidirectional"))
    )
    (net (code "69") (name "Net-(U$1-D6)") (class "Default")
      (node (ref "JP302") (pin "6") (pinfunction "6_6") (pintype "passive"))
      (node (ref "R319") (pin "1") (pinfunction "1_1") (pintype "passive"))
      (node (ref "R411") (pin "1") (pinfunction "1_1") (pintype "passive"))
      (node (ref "U$1") (pin "19") (pinfunction "D6_19") (pintype "bidirectional"))
    )
    (net (code "70") (name "Net-(U$1-D7)") (class "Default")
      (node (ref "JP302") (pin "5") (pinfunction "5_5") (pintype "passive"))
      (node (ref "R320") (pin "1") (pinfunction "1_1") (pintype "passive"))
      (node (ref "R409") (pin "1") (pinfunction "1_1") (pintype "passive"))
      (node (ref "U$1") (pin "20") (pinfunction "D7_20") (pintype "bidirectional"))
    )
    (net (code "71") (name "Net-(U$1-DAC)") (class "Default")
      (node (ref "JP301") (pin "7") (pinfunction "7_7") (pintype "passive"))
      (node (ref "R307") (pin "2") (pinfunction "2_2") (pintype "passive"))
      (node (ref "R407") (pin "2") (pinfunction "2_2") (pintype "passive"))
      (node (ref "U$1") (pin "6") (pinfunction "DAC_6") (pintype "bidirectional"))
    )
    (net (code "72") (name "Net-(U$1-RX)") (class "Default")
      (node (ref "JP301") (pin "9") (pinfunction "9_9") (pintype "passive"))
      (node (ref "R309") (pin "2") (pinfunction "2_2") (pintype "passive"))
      (node (ref "U$1") (pin "4") (pinfunction "RX_4") (pintype "bidirectional"))
    )
    (net (code "73") (name "Net-(U$1-TX)") (class "Default")
      (node (ref "JP301") (pin "10") (pinfunction "10_10") (pintype "passive"))
      (node (ref "R310") (pin "2") (pinfunction "2_2") (pintype "passive"))
      (node (ref "U$1") (pin "3") (pinfunction "TX_3") (pintype "bidirectional"))
    )
    (net (code "74") (name "Net-(U$1-WKP)") (class "Default")
      (node (ref "JP301") (pin "8") (pinfunction "8_8") (pintype "passive"))
      (node (ref "R308") (pin "2") (pinfunction "2_2") (pintype "passive"))
      (node (ref "R408") (pin "2") (pinfunction "2_2") (pintype "passive"))
      (node (ref "U$1") (pin "5") (pinfunction "WKP_5") (pintype "bidirectional"))
    )
    (net (code "75") (name "Net-(U$1-~{RST})") (class "Default")
      (node (ref "JP302") (pin "2") (pinfunction "2_2") (pintype "passive"))
      (node (ref "U$1") (pin "23") (pinfunction "~{RST}_23") (pintype "bidirectional"))
    )
    (net (code "76") (name "Net-(U$2-P1)") (class "Default")
      (node (ref "JP11") (pin "5") (pinfunction "5_5") (pintype "passive"))
      (node (ref "U$2") (pin "1") (pinfunction "P1_1") (pintype "bidirectional"))
    )
    (net (code "77") (name "Net-(U$2-P2)") (class "Default")
      (node (ref "JP12") (pin "5") (pinfunction "5_5") (pintype "passive"))
      (node (ref "U$2") (pin "2") (pinfunction "P2_2") (pintype "bidirectional"))
    )
    (net (code "78") (name "Net-(U$2-P3)") (class "Default")
      (node (ref "JP11") (pin "4") (pinfunction "4_4") (pintype "passive"))
      (node (ref "U$2") (pin "3") (pinfunction "P3_3") (pintype "bidirectional"))
    )
    (net (code "79") (name "Net-(U$2-P4)") (class "Default")
      (node (ref "JP12") (pin "4") (pinfunction "4_4") (pintype "passive"))
      (node (ref "U$2") (pin "4") (pinfunction "P4_4") (pintype "bidirectional"))
    )
    (net (code "80") (name "Net-(U$2-P5)") (class "Default")
      (node (ref "JP11") (pin "3") (pinfunction "3_3") (pintype "passive"))
      (node (ref "U$2") (pin "5") (pinfunction "P5_5") (pintype "bidirectional"))
    )
    (net (code "81") (name "Net-(U$2-P6)") (class "Default")
      (node (ref "JP12") (pin "3") (pinfunction "3_3") (pintype "passive"))
      (node (ref "U$2") (pin "6") (pinfunction "P6_6") (pintype "bidirectional"))
    )
    (net (code "82") (name "Net-(U$2-P7)") (class "Default")
      (node (ref "JP11") (pin "2") (pinfunction "2_2") (pintype "passive"))
      (node (ref "U$2") (pin "7") (pinfunction "P7_7") (pintype "bidirectional"))
    )
    (net (code "83") (name "Net-(U$2-P8)") (class "Default")
      (node (ref "JP12") (pin "2") (pinfunction "2_2") (pintype "passive"))
      (node (ref "U$2") (pin "8") (pinfunction "P8_8") (pintype "bidirectional"))
    )
    (net (code "84") (name "Net-(U$2-P9)") (class "Default")
      (node (ref "JP2") (pin "5") (pinfunction "5_5") (pintype "passive"))
      (node (ref "U$2") (pin "9") (pinfunction "P9_9") (pintype "bidirectional"))
    )
    (net (code "85") (name "Net-(U$2-P10)") (class "Default")
      (node (ref "JP10") (pin "5") (pinfunction "5_5") (pintype "passive"))
      (node (ref "U$2") (pin "10") (pinfunction "P10_10") (pintype "bidirectional"))
    )
    (net (code "86") (name "Net-(U$2-P11)") (class "Default")
      (node (ref "JP2") (pin "4") (pinfunction "4_4") (pintype "passive"))
      (node (ref "U$2") (pin "11") (pinfunction "P11_11") (pintype "bidirectional"))
    )
    (net (code "87") (name "Net-(U$2-P12)") (class "Default")
      (node (ref "JP10") (pin "4") (pinfunction "4_4") (pintype "passive"))
      (node (ref "U$2") (pin "12") (pinfunction "P12_12") (pintype "bidirectional"))
    )
    (net (code "88") (name "Net-(U$2-P13)") (class "Default")
      (node (ref "JP2") (pin "3") (pinfunction "3_3") (pintype "passive"))
      (node (ref "U$2") (pin "13") (pinfunction "P13_13") (pintype "bidirectional"))
    )
    (net (code "89") (name "Net-(U$2-P14)") (class "Default")
      (node (ref "JP10") (pin "3") (pinfunction "3_3") (pintype "passive"))
      (node (ref "U$2") (pin "14") (pinfunction "P14_14") (pintype "bidirectional"))
    )
    (net (code "90") (name "Net-(U$2-P15)") (class "Default")
      (node (ref "JP2") (pin "2") (pinfunction "2_2") (pintype "passive"))
      (node (ref "U$2") (pin "15") (pinfunction "P15_15") (pintype "bidirectional"))
    )
    (net (code "91") (name "Net-(U$2-P16)") (class "Default")
      (node (ref "JP10") (pin "2") (pinfunction "2_2") (pintype "passive"))
      (node (ref "U$2") (pin "16") (pinfunction "P16_16") (pintype "bidirectional"))
    )
    (net (code "92") (name "V_BATT") (class "Default")
      (node (ref "JP302") (pin "3") (pinfunction "3_3") (pintype "passive"))
      (node (ref "JP303") (pin "3") (pinfunction "3_3") (pintype "passive"))
      (node (ref "U$1") (pin "22") (pinfunction "VBAT_22") (pintype "power_in"))
    )
    (net (code "93") (name "unconnected-(JP1-D+-PadUSB_P)") (class "Default")
      (node (ref "JP1") (pin "USB_P") (pinfunction "D+_USB_P") (pintype "bidirectional"))
    )
    (net (code "94") (name "unconnected-(JP1-D--PadUSB_M)") (class "Default")
      (node (ref "JP1") (pin "USB_M") (pinfunction "D-_USB_M") (pintype "bidirectional"))
    )
    (net (code "95") (name "unconnected-(JP2-Pad1)") (class "Default")
      (node (ref "JP2") (pin "1") (pinfunction "1_1") (pintype "passive"))
    )
    (net (code "96") (name "unconnected-(JP2-Pad6)") (class "Default")
      (node (ref "JP2") (pin "6") (pinfunction "6_6") (pintype "passive"))
    )
    (net (code "97") (name "unconnected-(JP10-Pad1)") (class "Default")
      (node (ref "JP10") (pin "1") (pinfunction "1_1") (pintype "passive"))
    )
    (net (code "98") (name "unconnected-(JP10-Pad6)") (class "Default")
      (node (ref "JP10") (pin "6") (pinfunction "6_6") (pintype "passive"))
    )
    (net (code "99") (name "unconnected-(JP12-Pad1)") (class "Default")
      (node (ref "JP12") (pin "1") (pinfunction "1_1") (pintype "passive"))
    )
    (net (code "100") (name "unconnected-(JP101-Pad1)") (class "Default")
      (node (ref "JP101") (pin "1") (pinfunction "1_1") (pintype "passive"))
    )
    (net (code "101") (name "unconnected-(JP101-Pad2)") (class "Default")
      (node (ref "JP101") (pin "2") (pinfunction "2_2") (pintype "passive"))
    )
    (net (code "102") (name "unconnected-(JP101-Pad11)") (class "Default")
      (node (ref "JP101") (pin "11") (pinfunction "11_11") (pintype "passive"))
    )
    (net (code "103") (name "unconnected-(JP101-Pad12)") (class "Default")
      (node (ref "JP101") (pin "12") (pinfunction "12_12") (pintype "passive"))
    )
    (net (code "104") (name "unconnected-(JP203-Pad1)") (class "Default")
      (node (ref "JP203") (pin "1") (pinfunction "1_1") (pintype "passive"))
    )
    (net (code "105") (name "unconnected-(JP203-Pad2)") (class "Default")
      (node (ref "JP203") (pin "2") (pinfunction "2_2") (pintype "passive"))
    )
    (net (code "106") (name "unconnected-(JP203-Pad3)") (class "Default")
      (node (ref "JP203") (pin "3") (pinfunction "3_3") (pintype "passive"))
    )
    (net (code "107") (name "unconnected-(JP203-Pad4)") (class "Default")
      (node (ref "JP203") (pin "4") (pinfunction "4_4") (pintype "passive"))
    )
    (net (code "108") (name "unconnected-(JP203-Pad5)") (class "Default")
      (node (ref "JP203") (pin "5") (pinfunction "5_5") (pintype "passive"))
    )
    (net (code "109") (name "unconnected-(JP203-Pad6)") (class "Default")
      (node (ref "JP203") (pin "6") (pinfunction "6_6") (pintype "passive"))
    )
    (net (code "110") (name "unconnected-(JP203-Pad7)") (class "Default")
      (node (ref "JP203") (pin "7") (pinfunction "7_7") (pintype "passive"))
    )
    (net (code "111") (name "unconnected-(JP203-Pad8)") (class "Default")
      (node (ref "JP203") (pin "8") (pinfunction "8_8") (pintype "passive"))
    )
    (net (code "112") (name "unconnected-(JP203-Pad9)") (class "Default")
      (node (ref "JP203") (pin "9") (pinfunction "9_9") (pintype "passive"))
    )
    (net (code "113") (name "unconnected-(JP203-Pad10)") (class "Default")
      (node (ref "JP203") (pin "10") (pinfunction "10_10") (pintype "passive"))
    )
    (net (code "114") (name "unconnected-(JP203-Pad11)") (class "Default")
      (node (ref "JP203") (pin "11") (pinfunction "11_11") (pintype "passive"))
    )
    (net (code "115") (name "unconnected-(JP203-Pad12)") (class "Default")
      (node (ref "JP203") (pin "12") (pinfunction "12_12") (pintype "passive"))
    )
    (net (code "116") (name "unconnected-(JP204-Pad1)") (class "Default")
      (node (ref "JP204") (pin "1") (pinfunction "1_1") (pintype "passive"))
    )
    (net (code "117") (name "unconnected-(JP204-Pad2)") (class "Default")
      (node (ref "JP204") (pin "2") (pinfunction "2_2") (pintype "passive"))
    )
    (net (code "118") (name "unconnected-(JP204-Pad3)") (class "Default")
      (node (ref "JP204") (pin "3") (pinfunction "3_3") (pintype "passive"))
    )
    (net (code "119") (name "unconnected-(JP204-Pad4)") (class "Default")
      (node (ref "JP204") (pin "4") (pinfunction "4_4") (pintype "passive"))
    )
    (net (code "120") (name "unconnected-(JP204-Pad5)") (class "Default")
      (node (ref "JP204") (pin "5") (pinfunction "5_5") (pintype "passive"))
    )
    (net (code "121") (name "unconnected-(JP204-Pad6)") (class "Default")
      (node (ref "JP204") (pin "6") (pinfunction "6_6") (pintype "passive"))
    )
    (net (code "122") (name "unconnected-(JP204-Pad7)") (class "Default")
      (node (ref "JP204") (pin "7") (pinfunction "7_7") (pintype "passive"))
    )
    (net (code "123") (name "unconnected-(JP204-Pad8)") (class "Default")
      (node (ref "JP204") (pin "8") (pinfunction "8_8") (pintype "passive"))
    )
    (net (code "124") (name "unconnected-(JP204-Pad9)") (class "Default")
      (node (ref "JP204") (pin "9") (pinfunction "9_9") (pintype "passive"))
    )
    (net (code "125") (name "unconnected-(JP204-Pad10)") (class "Default")
      (node (ref "JP204") (pin "10") (pinfunction "10_10") (pintype "passive"))
    )
    (net (code "126") (name "unconnected-(JP204-Pad11)") (class "Default")
      (node (ref "JP204") (pin "11") (pinfunction "11_11") (pintype "passive"))
    )
    (net (code "127") (name "unconnected-(JP204-Pad12)") (class "Default")
      (node (ref "JP204") (pin "12") (pinfunction "12_12") (pintype "passive"))
    )
    (net (code "128") (name "unconnected-(JP205-Pad2)") (class "Default")
      (node (ref "JP205") (pin "2") (pinfunction "2_2") (pintype "passive"))
    )
    (net (code "129") (name "unconnected-(JP205-Pad3)") (class "Default")
      (node (ref "JP205") (pin "3") (pinfunction "3_3") (pintype "passive"))
    )
    (net (code "130") (name "unconnected-(JP205-Pad4)") (class "Default")
      (node (ref "JP205") (pin "4") (pinfunction "4_4") (pintype "passive"))
    )
    (net (code "131") (name "unconnected-(JP205-Pad5)") (class "Default")
      (node (ref "JP205") (pin "5") (pinfunction "5_5") (pintype "passive"))
    )
    (net (code "132") (name "unconnected-(JP205-Pad6)") (class "Default")
      (node (ref "JP205") (pin "6") (pinfunction "6_6") (pintype "passive"))
    )
    (net (code "133") (name "unconnected-(JP205-Pad7)") (class "Default")
      (node (ref "JP205") (pin "7") (pinfunction "7_7") (pintype "passive"))
    )
    (net (code "134") (name "unconnected-(JP205-Pad8)") (class "Default")
      (node (ref "JP205") (pin "8") (pinfunction "8_8") (pintype "passive"))
    )
    (net (code "135") (name "unconnected-(JP205-Pad9)") (class "Default")
      (node (ref "JP205") (pin "9") (pinfunction "9_9") (pintype "passive"))
    )
    (net (code "136") (name "unconnected-(JP206-Pad2)") (class "Default")
      (node (ref "JP206") (pin "2") (pinfunction "2_2") (pintype "passive"))
    )
    (net (code "137") (name "unconnected-(JP206-Pad3)") (class "Default")
      (node (ref "JP206") (pin "3") (pinfunction "3_3") (pintype "passive"))
    )
    (net (code "138") (name "unconnected-(JP206-Pad4)") (class "Default")
      (node (ref "JP206") (pin "4") (pinfunction "4_4") (pintype "passive"))
    )
    (net (code "139") (name "unconnected-(JP206-Pad5)") (class "Default")
      (node (ref "JP206") (pin "5") (pinfunction "5_5") (pintype "passive"))
    )
    (net (code "140") (name "unconnected-(JP206-Pad6)") (class "Default")
      (node (ref "JP206") (pin "6") (pinfunction "6_6") (pintype "passive"))
    )
    (net (code "141") (name "unconnected-(JP206-Pad7)") (class "Default")
      (node (ref "JP206") (pin "7") (pinfunction "7_7") (pintype "passive"))
    )
    (net (code "142") (name "unconnected-(JP206-Pad8)") (class "Default")
      (node (ref "JP206") (pin "8") (pinfunction "8_8") (pintype "passive"))
    )
    (net (code "143") (name "unconnected-(JP206-Pad9)") (class "Default")
      (node (ref "JP206") (pin "9") (pinfunction "9_9") (pintype "passive"))
    )
    (net (code "144") (name "unconnected-(JP207-Pad2)") (class "Default")
      (node (ref "JP207") (pin "2") (pinfunction "2_2") (pintype "passive"))
    )
    (net (code "145") (name "unconnected-(JP207-Pad3)") (class "Default")
      (node (ref "JP207") (pin "3") (pinfunction "3_3") (pintype "passive"))
    )
    (net (code "146") (name "unconnected-(JP207-Pad4)") (class "Default")
      (node (ref "JP207") (pin "4") (pinfunction "4_4") (pintype "passive"))
    )
    (net (code "147") (name "unconnected-(JP207-Pad5)") (class "Default")
      (node (ref "JP207") (pin "5") (pinfunction "5_5") (pintype "passive"))
    )
    (net (code "148") (name "unconnected-(JP207-Pad6)") (class "Default")
      (node (ref "JP207") (pin "6") (pinfunction "6_6") (pintype "passive"))
    )
    (net (code "149") (name "unconnected-(JP207-Pad7)") (class "Default")
      (node (ref "JP207") (pin "7") (pinfunction "7_7") (pintype "passive"))
    )
    (net (code "150") (name "unconnected-(JP207-Pad8)") (class "Default")
      (node (ref "JP207") (pin "8") (pinfunction "8_8") (pintype "passive"))
    )
    (net (code "151") (name "unconnected-(JP207-Pad9)") (class "Default")
      (node (ref "JP207") (pin "9") (pinfunction "9_9") (pintype "passive"))
    )
    (net (code "152") (name "unconnected-(JP208-Pad2)") (class "Default")
      (node (ref "JP208") (pin "2") (pinfunction "2_2") (pintype "passive"))
    )
    (net (code "153") (name "unconnected-(JP208-Pad3)") (class "Default")
      (node (ref "JP208") (pin "3") (pinfunction "3_3") (pintype "passive"))
    )
    (net (code "154") (name "unconnected-(JP208-Pad4)") (class "Default")
      (node (ref "JP208") (pin "4") (pinfunction "4_4") (pintype "passive"))
    )
    (net (code "155") (name "unconnected-(JP208-Pad5)") (class "Default")
      (node (ref "JP208") (pin "5") (pinfunction "5_5") (pintype "passive"))
    )
    (net (code "156") (name "unconnected-(JP208-Pad6)") (class "Default")
      (node (ref "JP208") (pin "6") (pinfunction "6_6") (pintype "passive"))
    )
    (net (code "157") (name "unconnected-(JP208-Pad7)") (class "Default")
      (node (ref "JP208") (pin "7") (pinfunction "7_7") (pintype "passive"))
    )
    (net (code "158") (name "unconnected-(JP208-Pad8)") (class "Default")
      (node (ref "JP208") (pin "8") (pinfunction "8_8") (pintype "passive"))
    )
    (net (code "159") (name "unconnected-(JP208-Pad9)") (class "Default")
      (node (ref "JP208") (pin "9") (pinfunction "9_9") (pintype "passive"))
    )
    (net (code "160") (name "unconnected-(JP209-Pad2)") (class "Default")
      (node (ref "JP209") (pin "2") (pinfunction "2_2") (pintype "passive"))
    )
    (net (code "161") (name "unconnected-(JP209-Pad3)") (class "Default")
      (node (ref "JP209") (pin "3") (pinfunction "3_3") (pintype "passive"))
    )
    (net (code "162") (name "unconnected-(JP209-Pad4)") (class "Default")
      (node (ref "JP209") (pin "4") (pinfunction "4_4") (pintype "passive"))
    )
    (net (code "163") (name "unconnected-(JP209-Pad5)") (class "Default")
      (node (ref "JP209") (pin "5") (pinfunction "5_5") (pintype "passive"))
    )
    (net (code "164") (name "unconnected-(JP209-Pad6)") (class "Default")
      (node (ref "JP209") (pin "6") (pinfunction "6_6") (pintype "passive"))
    )
    (net (code "165") (name "unconnected-(JP209-Pad7)") (class "Default")
      (node (ref "JP209") (pin "7") (pinfunction "7_7") (pintype "passive"))
    )
    (net (code "166") (name "unconnected-(JP209-Pad8)") (class "Default")
      (node (ref "JP209") (pin "8") (pinfunction "8_8") (pintype "passive"))
    )
    (net (code "167") (name "unconnected-(JP209-Pad9)") (class "Default")
      (node (ref "JP209") (pin "9") (pinfunction "9_9") (pintype "passive"))
    )
    (net (code "168") (name "unconnected-(JP210-Pad2)") (class "Default")
      (node (ref "JP210") (pin "2") (pinfunction "2_2") (pintype "passive"))
    )
    (net (code "169") (name "unconnected-(JP210-Pad3)") (class "Default")
      (node (ref "JP210") (pin "3") (pinfunction "3_3") (pintype "passive"))
    )
    (net (code "170") (name "unconnected-(JP210-Pad4)") (class "Default")
      (node (ref "JP210") (pin "4") (pinfunction "4_4") (pintype "passive"))
    )
    (net (code "171") (name "unconnected-(JP210-Pad5)") (class "Default")
      (node (ref "JP210") (pin "5") (pinfunction "5_5") (pintype "passive"))
    )
    (net (code "172") (name "unconnected-(JP210-Pad6)") (class "Default")
      (node (ref "JP210") (pin "6") (pinfunction "6_6") (pintype "passive"))
    )
    (net (code "173") (name "unconnected-(JP210-Pad7)") (class "Default")
      (node (ref "JP210") (pin "7") (pinfunction "7_7") (pintype "passive"))
    )
    (net (code "174") (name "unconnected-(JP210-Pad8)") (class "Default")
      (node (ref "JP210") (pin "8") (pinfunction "8_8") (pintype "passive"))
    )
    (net (code "175") (name "unconnected-(JP210-Pad9)") (class "Default")
      (node (ref "JP210") (pin "9") (pinfunction "9_9") (pintype "passive"))
    )
    (net (code "176") (name "unconnected-(JP211-Pad2)") (class "Default")
      (node (ref "JP211") (pin "2") (pinfunction "2_2") (pintype "passive"))
    )
    (net (code "177") (name "unconnected-(JP211-Pad3)") (class "Default")
      (node (ref "JP211") (pin "3") (pinfunction "3_3") (pintype "passive"))
    )
    (net (code "178") (name "unconnected-(JP211-Pad4)") (class "Default")
      (node (ref "JP211") (pin "4") (pinfunction "4_4") (pintype "passive"))
    )
    (net (code "179") (name "unconnected-(JP211-Pad5)") (class "Default")
      (node (ref "JP211") (pin "5") (pinfunction "5_5") (pintype "passive"))
    )
    (net (code "180") (name "unconnected-(JP211-Pad6)") (class "Default")
      (node (ref "JP211") (pin "6") (pinfunction "6_6") (pintype "passive"))
    )
    (net (code "181") (name "unconnected-(JP211-Pad7)") (class "Default")
      (node (ref "JP211") (pin "7") (pinfunction "7_7") (pintype "passive"))
    )
    (net (code "182") (name "unconnected-(JP211-Pad8)") (class "Default")
      (node (ref "JP211") (pin "8") (pinfunction "8_8") (pintype "passive"))
    )
    (net (code "183") (name "unconnected-(JP211-Pad9)") (class "Default")
      (node (ref "JP211") (pin "9") (pinfunction "9_9") (pintype "passive"))
    )
    (net (code "184") (name "unconnected-(JP212-Pad2)") (class "Default")
      (node (ref "JP212") (pin "2") (pinfunction "2_2") (pintype "passive"))
    )
    (net (code "185") (name "unconnected-(JP212-Pad3)") (class "Default")
      (node (ref "JP212") (pin "3") (pinfunction "3_3") (pintype "passive"))
    )
    (net (code "186") (name "unconnected-(JP212-Pad4)") (class "Default")
      (node (ref "JP212") (pin "4") (pinfunction "4_4") (pintype "passive"))
    )
    (net (code "187") (name "unconnected-(JP212-Pad5)") (class "Default")
      (node (ref "JP212") (pin "5") (pinfunction "5_5") (pintype "passive"))
    )
    (net (code "188") (name "unconnected-(JP212-Pad6)") (class "Default")
      (node (ref "JP212") (pin "6") (pinfunction "6_6") (pintype "passive"))
    )
    (net (code "189") (name "unconnected-(JP212-Pad7)") (class "Default")
      (node (ref "JP212") (pin "7") (pinfunction "7_7") (pintype "passive"))
    )
    (net (code "190") (name "unconnected-(JP212-Pad8)") (class "Default")
      (node (ref "JP212") (pin "8") (pinfunction "8_8") (pintype "passive"))
    )
    (net (code "191") (name "unconnected-(JP212-Pad9)") (class "Default")
      (node (ref "JP212") (pin "9") (pinfunction "9_9") (pintype "passive"))
    )
    (net (code "192") (name "unconnected-(JP213-Pad1)") (class "Default")
      (node (ref "JP213") (pin "1") (pinfunction "1_1") (pintype "passive"))
    )
    (net (code "193") (name "unconnected-(JP213-Pad2)") (class "Default")
      (node (ref "JP213") (pin "2") (pinfunction "2_2") (pintype "passive"))
    )
    (net (code "194") (name "unconnected-(JP213-Pad3)") (class "Default")
      (node (ref "JP213") (pin "3") (pinfunction "3_3") (pintype "passive"))
    )
    (net (code "195") (name "unconnected-(JP213-Pad4)") (class "Default")
      (node (ref "JP213") (pin "4") (pinfunction "4_4") (pintype "passive"))
    )
    (net (code "196") (name "unconnected-(JP213-Pad5)") (class "Default")
      (node (ref "JP213") (pin "5") (pinfunction "5_5") (pintype "passive"))
    )
    (net (code "197") (name "unconnected-(JP213-Pad6)") (class "Default")
      (node (ref "JP213") (pin "6") (pinfunction "6_6") (pintype "passive"))
    )
    (net (code "198") (name "unconnected-(JP213-Pad7)") (class "Default")
      (node (ref "JP213") (pin "7") (pinfunction "7_7") (pintype "passive"))
    )
    (net (code "199") (name "unconnected-(JP213-Pad8)") (class "Default")
      (node (ref "JP213") (pin "8") (pinfunction "8_8") (pintype "passive"))
    )
    (net (code "200") (name "unconnected-(JP213-Pad9)") (class "Default")
      (node (ref "JP213") (pin "9") (pinfunction "9_9") (pintype "passive"))
    )
    (net (code "201") (name "unconnected-(JP213-Pad10)") (class "Default")
      (node (ref "JP213") (pin "10") (pinfunction "10_10") (pintype "passive"))
    )
    (net (code "202") (name "unconnected-(JP213-Pad11)") (class "Default")
      (node (ref "JP213") (pin "11") (pinfunction "11_11") (pintype "passive"))
    )
    (net (code "203") (name "unconnected-(JP213-Pad12)") (class "Default")
      (node (ref "JP213") (pin "12") (pinfunction "12_12") (pintype "passive"))
    )
    (net (code "204") (name "unconnected-(JP214-Pad1)") (class "Default")
      (node (ref "JP214") (pin "1") (pinfunction "1_1") (pintype "passive"))
    )
    (net (code "205") (name "unconnected-(JP214-Pad2)") (class "Default")
      (node (ref "JP214") (pin "2") (pinfunction "2_2") (pintype "passive"))
    )
    (net (code "206") (name "unconnected-(JP214-Pad3)") (class "Default")
      (node (ref "JP214") (pin "3") (pinfunction "3_3") (pintype "passive"))
    )
    (net (code "207") (name "unconnected-(JP214-Pad4)") (class "Default")
      (node (ref "JP214") (pin "4") (pinfunction "4_4") (pintype "passive"))
    )
    (net (code "208") (name "unconnected-(JP214-Pad5)") (class "Default")
      (node (ref "JP214") (pin "5") (pinfunction "5_5") (pintype "passive"))
    )
    (net (code "209") (name "unconnected-(JP214-Pad6)") (class "Default")
      (node (ref "JP214") (pin "6") (pinfunction "6_6") (pintype "passive"))
    )
    (net (code "210") (name "unconnected-(JP214-Pad7)") (class "Default")
      (node (ref "JP214") (pin "7") (pinfunction "7_7") (pintype "passive"))
    )
    (net (code "211") (name "unconnected-(JP214-Pad8)") (class "Default")
      (node (ref "JP214") (pin "8") (pinfunction "8_8") (pintype "passive"))
    )
    (net (code "212") (name "unconnected-(JP214-Pad9)") (class "Default")
      (node (ref "JP214") (pin "9") (pinfunction "9_9") (pintype "passive"))
    )
    (net (code "213") (name "unconnected-(JP214-Pad10)") (class "Default")
      (node (ref "JP214") (pin "10") (pinfunction "10_10") (pintype "passive"))
    )
    (net (code "214") (name "unconnected-(JP214-Pad11)") (class "Default")
      (node (ref "JP214") (pin "11") (pinfunction "11_11") (pintype "passive"))
    )
    (net (code "215") (name "unconnected-(JP214-Pad12)") (class "Default")
      (node (ref "JP214") (pin "12") (pinfunction "12_12") (pintype "passive"))
    )
    (net (code "216") (name "unconnected-(JP303-Pad2)") (class "Default")
      (node (ref "JP303") (pin "2") (pinfunction "2_2") (pintype "passive"))
    )
    (net (code "217") (name "unconnected-(R301-Pad1)") (class "Default")
      (node (ref "R301") (pin "1") (pinfunction "1_1") (pintype "passive"))
    )
    (net (code "218") (name "unconnected-(R302-Pad1)") (class "Default")
      (node (ref "R302") (pin "1") (pinfunction "1_1") (pintype "passive"))
    )
    (net (code "219") (name "unconnected-(R303-Pad1)") (class "Default")
      (node (ref "R303") (pin "1") (pinfunction "1_1") (pintype "passive"))
    )
    (net (code "220") (name "unconnected-(R304-Pad1)") (class "Default")
      (node (ref "R304") (pin "1") (pinfunction "1_1") (pintype "passive"))
    )
    (net (code "221") (name "unconnected-(R305-Pad1)") (class "Default")
      (node (ref "R305") (pin "1") (pinfunction "1_1") (pintype "passive"))
    )
    (net (code "222") (name "unconnected-(R306-Pad1)") (class "Default")
      (node (ref "R306") (pin "1") (pinfunction "1_1") (pintype "passive"))
    )
    (net (code "223") (name "unconnected-(R307-Pad1)") (class "Default")
      (node (ref "R307") (pin "1") (pinfunction "1_1") (pintype "passive"))
    )
    (net (code "224") (name "unconnected-(R308-Pad1)") (class "Default")
      (node (ref "R308") (pin "1") (pinfunction "1_1") (pintype "passive"))
    )
    (net (code "225") (name "unconnected-(R309-Pad1)") (class "Default")
      (node (ref "R309") (pin "1") (pinfunction "1_1") (pintype "passive"))
    )
    (net (code "226") (name "unconnected-(R310-Pad1)") (class "Default")
      (node (ref "R310") (pin "1") (pinfunction "1_1") (pintype "passive"))
    )
    (net (code "227") (name "unconnected-(R311-Pad1)") (class "Default")
      (node (ref "R311") (pin "1") (pinfunction "1_1") (pintype "passive"))
    )
    (net (code "228") (name "unconnected-(R312-Pad2)") (class "Default")
      (node (ref "R312") (pin "2") (pinfunction "2_2") (pintype "passive"))
    )
    (net (code "229") (name "unconnected-(R313-Pad1)") (class "Default")
      (node (ref "R313") (pin "1") (pinfunction "1_1") (pintype "passive"))
    )
    (net (code "230") (name "unconnected-(R314-Pad1)") (class "Default")
      (node (ref "R314") (pin "1") (pinfunction "1_1") (pintype "passive"))
    )
    (net (code "231") (name "unconnected-(R315-Pad1)") (class "Default")
      (node (ref "R315") (pin "1") (pinfunction "1_1") (pintype "passive"))
    )
    (net (code "232") (name "unconnected-(R316-Pad1)") (class "Default")
      (node (ref "R316") (pin "1") (pinfunction "1_1") (pintype "passive"))
    )
    (net (code "233") (name "unconnected-(R317-Pad2)") (class "Default")
      (node (ref "R317") (pin "2") (pinfunction "2_2") (pintype "passive"))
    )
    (net (code "234") (name "unconnected-(R318-Pad2)") (class "Default")
      (node (ref "R318") (pin "2") (pinfunction "2_2") (pintype "passive"))
    )
    (net (code "235") (name "unconnected-(R319-Pad2)") (class "Default")
      (node (ref "R319") (pin "2") (pinfunction "2_2") (pintype "passive"))
    )
    (net (code "236") (name "unconnected-(R320-Pad2)") (class "Default")
      (node (ref "R320") (pin "2") (pinfunction "2_2") (pintype "passive"))
    )
  )
)
